# SCH_U-Blox_Neo_shield_for_Wemos_D1_Mini_.net
KiCad netlist of a schematic drawn in EasyEDA
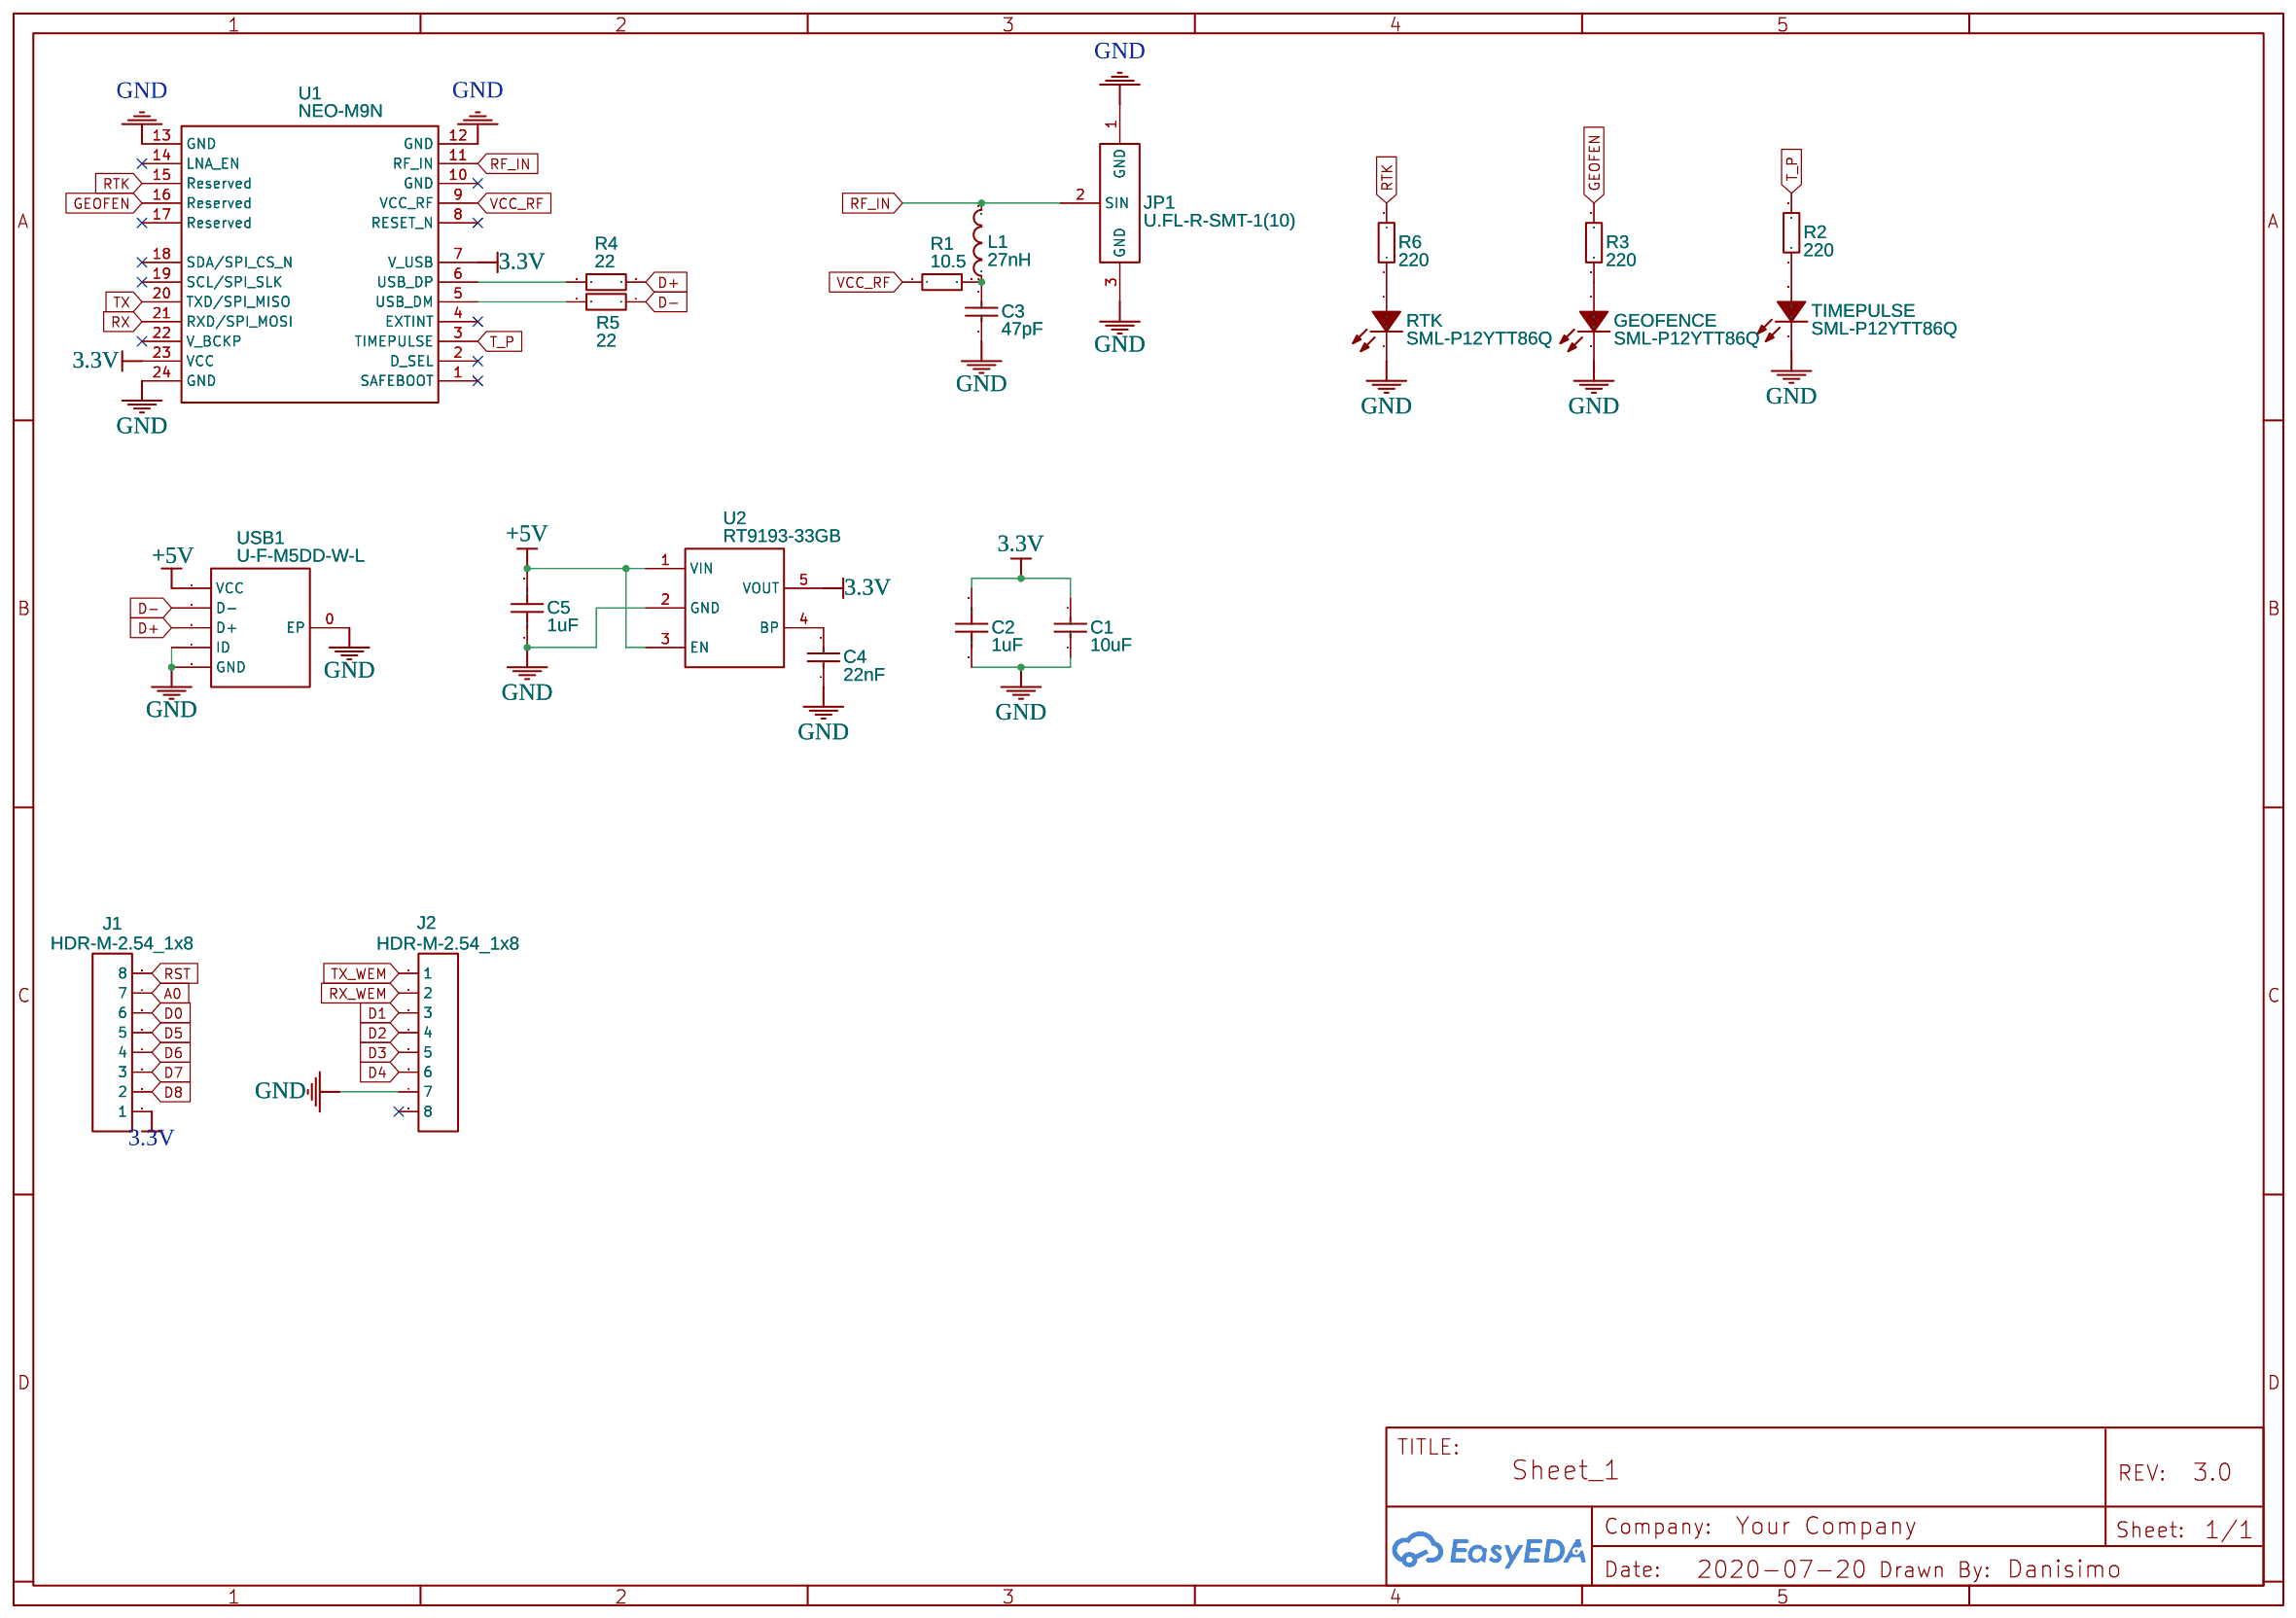
[diagram p0: schematic sheet]

(export (version "E")
  (design (tool "Eeschema 10.0.6"))
  (components
    (comp (ref "C1")
      (value "10uF")
      (fields
        (field (name "BOM_Manufacturer Part") "CL05A106MQ5NUNC")
        (field (name "BOM_Supplier Part") "C15525")
      )
      (libsource (lib "") (part "CL05A106MQ5NUNC"))
    )
    (comp (ref "C2")
      (value "1uF")
      (fields
        (field (name "BOM_Manufacturer Part") "CL05A105KA5NQNC")
        (field (name "BOM_Supplier Part") "C52923")
      )
      (libsource (lib "") (part "CL05A105KA5NQNC"))
    )
    (comp (ref "C3")
      (value "47pF")
      (fields
        (field (name "BOM_Manufacturer Part") "0402CG470J500NT")
        (field (name "BOM_Supplier Part") "C1567")
      )
      (libsource (lib "") (part "0402CG470J500NT"))
    )
    (comp (ref "C4")
      (value "22nF")
      (fields
        (field (name "BOM_Manufacturer Part") "0402B223K500NT")
        (field (name "BOM_Supplier Part") "C1532")
      )
      (libsource (lib "") (part "0402B223K500NT"))
    )
    (comp (ref "C5")
      (value "1uF")
      (fields
        (field (name "BOM_Manufacturer Part") "CL05A105KA5NQNC")
        (field (name "BOM_Supplier Part") "C52923")
      )
      (libsource (lib "") (part "CL05A105KA5NQNC"))
    )
    (comp (ref "GEOFENCE")
      (value "SML-P12YTT86Q")
      (fields (field (name "BOM_Supplier Part") "C123071"))
      (libsource (lib "") (part "SML-P12YTT86Q_2"))
    )
    (comp (ref "J1")
      (value "HDR-M-2.54_1x8")
      (fields (field (name "BOM_Supplier Part") "C190820"))
      (libsource (lib "") (part "HDR-M-2.54_1x8"))
    )
    (comp (ref "J2")
      (value "HDR-M-2.54_1x8")
      (fields (field (name "BOM_Supplier Part") "C190820"))
      (libsource (lib "") (part "HDR-M-2.54_1x8_1"))
    )
    (comp (ref "JP1")
      (value "U.FL-R-SMT-1(10)")
      (fields (field (name "BOM_Supplier Part") "C88373"))
      (libsource (lib "") (part "U.FL-R-SMT-1(10)"))
    )
    (comp (ref "L1")
      (value "27nH")
      (fields
        (field (name "BOM_Manufacturer Part") "SDCL1005C27NJTDF")
        (field (name "BOM_Supplier Part") "C18830")
      )
      (libsource (lib "") (part "SDCL1005C27NJTDF"))
    )
    (comp (ref "R1")
      (value "10.5")
      (fields
        (field (name "BOM_Manufacturer Part") "0603WAF105JT5E")
        (field (name "BOM_Supplier Part") "C22856")
      )
      (libsource (lib "") (part "0603WAF105JT5E"))
    )
    (comp (ref "R2")
      (value "220")
      (fields
        (field (name "BOM_Manufacturer Part") "0402WGF2200TCE")
        (field (name "BOM_Supplier Part") "C25091")
      )
      (libsource (lib "") (part "0402WGF2200TCE"))
    )
    (comp (ref "R3")
      (value "220")
      (fields
        (field (name "BOM_Manufacturer Part") "0402WGF2200TCE")
        (field (name "BOM_Supplier Part") "C25091")
      )
      (libsource (lib "") (part "0402WGF2200TCE"))
    )
    (comp (ref "R4")
      (value "22")
      (fields
        (field (name "BOM_Manufacturer Part") "0402WGF220JTCE")
        (field (name "BOM_Supplier Part") "C25092")
      )
      (libsource (lib "") (part "0402WGF220JTCE"))
    )
    (comp (ref "R5")
      (value "22")
      (fields
        (field (name "BOM_Manufacturer Part") "0402WGF220JTCE")
        (field (name "BOM_Supplier Part") "C25092")
      )
      (libsource (lib "") (part "0402WGF220JTCE_1"))
    )
    (comp (ref "R6")
      (value "220")
      (fields
        (field (name "BOM_Manufacturer Part") "0402WGF2200TCE")
        (field (name "BOM_Supplier Part") "C25091")
      )
      (libsource (lib "") (part "0402WGF2200TCE"))
    )
    (comp (ref "RTK")
      (value "SML-P12YTT86Q")
      (fields (field (name "BOM_Supplier Part") "C123071"))
      (libsource (lib "") (part "SML-P12YTT86Q_1"))
    )
    (comp (ref "TIMEPULSE")
      (value "SML-P12YTT86Q")
      (fields (field (name "BOM_Supplier Part") "C123071"))
      (libsource (lib "") (part "SML-P12YTT86Q"))
    )
    (comp (ref "U1") (value "NEO-M9N") (libsource (lib "") (part "NEO-M9N")))
    (comp (ref "U2")
      (value "RT9193-33GB")
      (fields (field (name "BOM_Supplier Part") "C15651"))
      (libsource (lib "") (part "RT9193-33GB"))
    )
    (comp (ref "USB1")
      (value "U-F-M5DD-W-L")
      (fields (field (name "BOM_Supplier Part") "C145792"))
      (libsource (lib "") (part "U-F-M5DD-W-L"))
    )
  )
  (nets
    (net (code "1") (name "+5V") (class "Default")
      (node (ref "C5") (pin "2") (pinfunction "2_2") (pintype "unspecified"))
      (node (ref "U2") (pin "1") (pinfunction "VIN_1") (pintype "unspecified"))
      (node (ref "U2") (pin "3") (pinfunction "EN_3") (pintype "unspecified"))
      (node (ref "USB1") (pin "1") (pinfunction "VCC_1") (pintype "input"))
    )
    (net (code "2") (name "3.3V") (class "Default")
      (node (ref "C1") (pin "2") (pinfunction "2_2") (pintype "input"))
      (node (ref "C2") (pin "2") (pinfunction "2_2") (pintype "unspecified"))
      (node (ref "J1") (pin "1") (pinfunction "1_1") (pintype "unspecified"))
      (node (ref "U1") (pin "23") (pinfunction "VCC_23") (pintype "unspecified"))
      (node (ref "U1") (pin "7") (pinfunction "V_USB_7") (pintype "unspecified"))
      (node (ref "U2") (pin "5") (pinfunction "VOUT_5") (pintype "unspecified"))
    )
    (net (code "3") (name "A0") (class "Default")
      (node (ref "J1") (pin "7") (pinfunction "7_7") (pintype "unspecified"))
    )
    (net (code "4") (name "D+") (class "Default")
      (node (ref "R4") (pin "2") (pinfunction "2_2") (pintype "input"))
      (node (ref "USB1") (pin "3") (pinfunction "D+_3") (pintype "input"))
    )
    (net (code "5") (name "D-") (class "Default")
      (node (ref "R5") (pin "1") (pinfunction "1_1") (pintype "input"))
      (node (ref "USB1") (pin "2") (pinfunction "D-_2") (pintype "input"))
    )
    (net (code "6") (name "D0") (class "Default")
      (node (ref "J1") (pin "6") (pinfunction "6_6") (pintype "unspecified"))
    )
    (net (code "7") (name "D1") (class "Default")
      (node (ref "J2") (pin "3") (pinfunction "3_3") (pintype "unspecified"))
    )
    (net (code "8") (name "D2") (class "Default")
      (node (ref "J2") (pin "4") (pinfunction "4_4") (pintype "unspecified"))
    )
    (net (code "9") (name "D3") (class "Default")
      (node (ref "J2") (pin "5") (pinfunction "5_5") (pintype "unspecified"))
    )
    (net (code "10") (name "D4") (class "Default")
      (node (ref "J2") (pin "6") (pinfunction "6_6") (pintype "unspecified"))
    )
    (net (code "11") (name "D5") (class "Default")
      (node (ref "J1") (pin "5") (pinfunction "5_5") (pintype "unspecified"))
    )
    (net (code "12") (name "D6") (class "Default")
      (node (ref "J1") (pin "4") (pinfunction "4_4") (pintype "unspecified"))
    )
    (net (code "13") (name "D7") (class "Default")
      (node (ref "J1") (pin "3") (pinfunction "3_3") (pintype "unspecified"))
    )
    (net (code "14") (name "D8") (class "Default")
      (node (ref "J1") (pin "2") (pinfunction "2_2") (pintype "unspecified"))
    )
    (net (code "15") (name "GEOFEN") (class "Default")
      (node (ref "R3") (pin "2") (pinfunction "2_2") (pintype "input"))
      (node (ref "U1") (pin "16") (pinfunction "Reserved_16") (pintype "unspecified"))
    )
    (net (code "16") (name "GND") (class "Default")
      (node (ref "C1") (pin "1") (pinfunction "1_1") (pintype "input"))
      (node (ref "C2") (pin "1") (pinfunction "1_1") (pintype "unspecified"))
      (node (ref "C3") (pin "1") (pinfunction "1_1") (pintype "input"))
      (node (ref "C4") (pin "1") (pinfunction "1_1") (pintype "input"))
      (node (ref "C5") (pin "1") (pinfunction "1_1") (pintype "unspecified"))
      (node (ref "GEOFENCE") (pin "1") (pinfunction "1_1") (pintype "unspecified"))
      (node (ref "J2") (pin "7") (pinfunction "7_7") (pintype "unspecified"))
      (node (ref "JP1") (pin "1") (pinfunction "GND_1") (pintype "unspecified"))
      (node (ref "JP1") (pin "3") (pinfunction "GND_3") (pintype "unspecified"))
      (node (ref "RTK") (pin "1") (pinfunction "1_1") (pintype "unspecified"))
      (node (ref "TIMEPULSE") (pin "1") (pinfunction "1_1") (pintype "unspecified"))
      (node (ref "U1") (pin "12") (pinfunction "GND_12") (pintype "unspecified"))
      (node (ref "U1") (pin "13") (pinfunction "GND_13") (pintype "unspecified"))
      (node (ref "U1") (pin "24") (pinfunction "GND_24") (pintype "unspecified"))
      (node (ref "U2") (pin "2") (pinfunction "GND_2") (pintype "unspecified"))
      (node (ref "USB1") (pin "0") (pinfunction "EP_0") (pintype "unspecified"))
      (node (ref "USB1") (pin "4") (pinfunction "ID_4") (pintype "input"))
      (node (ref "USB1") (pin "5") (pinfunction "GND_5") (pintype "input"))
    )
    (net (code "17") (name "Net-(C3-Pad2)") (class "Default")
      (node (ref "C3") (pin "2") (pinfunction "2_2") (pintype "input"))
      (node (ref "L1") (pin "1") (pinfunction "1_1") (pintype "unspecified"))
      (node (ref "R1") (pin "2") (pinfunction "2_2") (pintype "input"))
    )
    (net (code "18") (name "Net-(GEOFENCE-Pad2)") (class "Default")
      (node (ref "GEOFENCE") (pin "2") (pinfunction "2_2") (pintype "unspecified"))
      (node (ref "R3") (pin "1") (pinfunction "1_1") (pintype "input"))
    )
    (net (code "19") (name "Net-(R2-Pad1)") (class "Default")
      (node (ref "R2") (pin "1") (pinfunction "1_1") (pintype "input"))
      (node (ref "TIMEPULSE") (pin "2") (pinfunction "2_2") (pintype "unspecified"))
    )
    (net (code "20") (name "Net-(R6-Pad1)") (class "Default")
      (node (ref "R6") (pin "1") (pinfunction "1_1") (pintype "input"))
      (node (ref "RTK") (pin "2") (pinfunction "2_2") (pintype "unspecified"))
    )
    (net (code "21") (name "Net-(U1-USB_DM)") (class "Default")
      (node (ref "R5") (pin "2") (pinfunction "2_2") (pintype "input"))
      (node (ref "U1") (pin "5") (pinfunction "USB_DM_5") (pintype "unspecified"))
    )
    (net (code "22") (name "Net-(U1-USB_DP)") (class "Default")
      (node (ref "R4") (pin "1") (pinfunction "1_1") (pintype "input"))
      (node (ref "U1") (pin "6") (pinfunction "USB_DP_6") (pintype "unspecified"))
    )
    (net (code "23") (name "Net-(U2-BP)") (class "Default")
      (node (ref "C4") (pin "2") (pinfunction "2_2") (pintype "input"))
      (node (ref "U2") (pin "4") (pinfunction "BP_4") (pintype "unspecified"))
    )
    (net (code "24") (name "RF_IN") (class "Default")
      (node (ref "JP1") (pin "2") (pinfunction "SIN_2") (pintype "unspecified"))
      (node (ref "L1") (pin "2") (pinfunction "2_2") (pintype "unspecified"))
      (node (ref "U1") (pin "11") (pinfunction "RF_IN_11") (pintype "unspecified"))
    )
    (net (code "25") (name "RST") (class "Default")
      (node (ref "J1") (pin "8") (pinfunction "8_8") (pintype "unspecified"))
    )
    (net (code "26") (name "RTK") (class "Default")
      (node (ref "R6") (pin "2") (pinfunction "2_2") (pintype "input"))
      (node (ref "U1") (pin "15") (pinfunction "Reserved_15") (pintype "unspecified"))
    )
    (net (code "27") (name "RX") (class "Default")
      (node (ref "U1") (pin "21") (pinfunction "RXD/SPI_MOSI_21") (pintype "unspecified"))
    )
    (net (code "28") (name "RX_WEM") (class "Default")
      (node (ref "J2") (pin "2") (pinfunction "2_2") (pintype "unspecified"))
    )
    (net (code "29") (name "TX") (class "Default")
      (node (ref "U1") (pin "20") (pinfunction "TXD/SPI_MISO_20") (pintype "unspecified"))
    )
    (net (code "30") (name "TX_WEM") (class "Default")
      (node (ref "J2") (pin "1") (pinfunction "1_1") (pintype "unspecified"))
    )
    (net (code "31") (name "T_P") (class "Default")
      (node (ref "R2") (pin "2") (pinfunction "2_2") (pintype "input"))
      (node (ref "U1") (pin "3") (pinfunction "TIMEPULSE_3") (pintype "unspecified"))
    )
    (net (code "32") (name "VCC_RF") (class "Default")
      (node (ref "R1") (pin "1") (pinfunction "1_1") (pintype "input"))
      (node (ref "U1") (pin "9") (pinfunction "VCC_RF_9") (pintype "unspecified"))
    )
    (net (code "33") (name "unconnected-(J2-Pad8)") (class "Default")
      (node (ref "J2") (pin "8") (pinfunction "8_8") (pintype "unspecified+no_connect"))
    )
    (net (code "34") (name "unconnected-(U1-D_SEL-Pad2)") (class "Default")
      (node (ref "U1") (pin "2") (pinfunction "D_SEL_2") (pintype "unspecified+no_connect"))
    )
    (net (code "35") (name "unconnected-(U1-EXTINT-Pad4)") (class "Default")
      (node (ref "U1") (pin "4") (pinfunction "EXTINT_4") (pintype "unspecified+no_connect"))
    )
    (net (code "36") (name "unconnected-(U1-GND-Pad10)") (class "Default")
      (node (ref "U1") (pin "10") (pinfunction "GND_10") (pintype "unspecified+no_connect"))
    )
    (net (code "37") (name "unconnected-(U1-LNA_EN-Pad14)") (class "Default")
      (node (ref "U1") (pin "14") (pinfunction "LNA_EN_14") (pintype "unspecified+no_connect"))
    )
    (net (code "38") (name "unconnected-(U1-RESET_N-Pad8)") (class "Default")
      (node (ref "U1") (pin "8") (pinfunction "RESET_N_8") (pintype "unspecified+no_connect"))
    )
    (net (code "39") (name "unconnected-(U1-Reserved-Pad17)") (class "Default")
      (node (ref "U1") (pin "17") (pinfunction "Reserved_17") (pintype "unspecified+no_connect"))
    )
    (net (code "40") (name "unconnected-(U1-SAFEBOOT-Pad1)") (class "Default")
      (node (ref "U1") (pin "1") (pinfunction "SAFEBOOT_1") (pintype "unspecified+no_connect"))
    )
    (net (code "41") (name "unconnected-(U1-SCL{slash}SPI_SLK-Pad19)") (class "Default")
      (node (ref "U1") (pin "19") (pinfunction "SCL/SPI_SLK_19") (pintype "unspecified+no_connect"))
    )
    (net (code "42") (name "unconnected-(U1-SDA{slash}SPI_CS_N-Pad18)") (class "Default")
      (node (ref "U1") (pin "18") (pinfunction "SDA/SPI_CS_N_18") (pintype "unspecified+no_connect"))
    )
    (net (code "43") (name "unconnected-(U1-V_BCKP-Pad22)") (class "Default")
      (node (ref "U1") (pin "22") (pinfunction "V_BCKP_22") (pintype "unspecified+no_connect"))
    )
  )
)
